# RH044_2.net
KiCad netlist of a schematic drawn in EAGLE
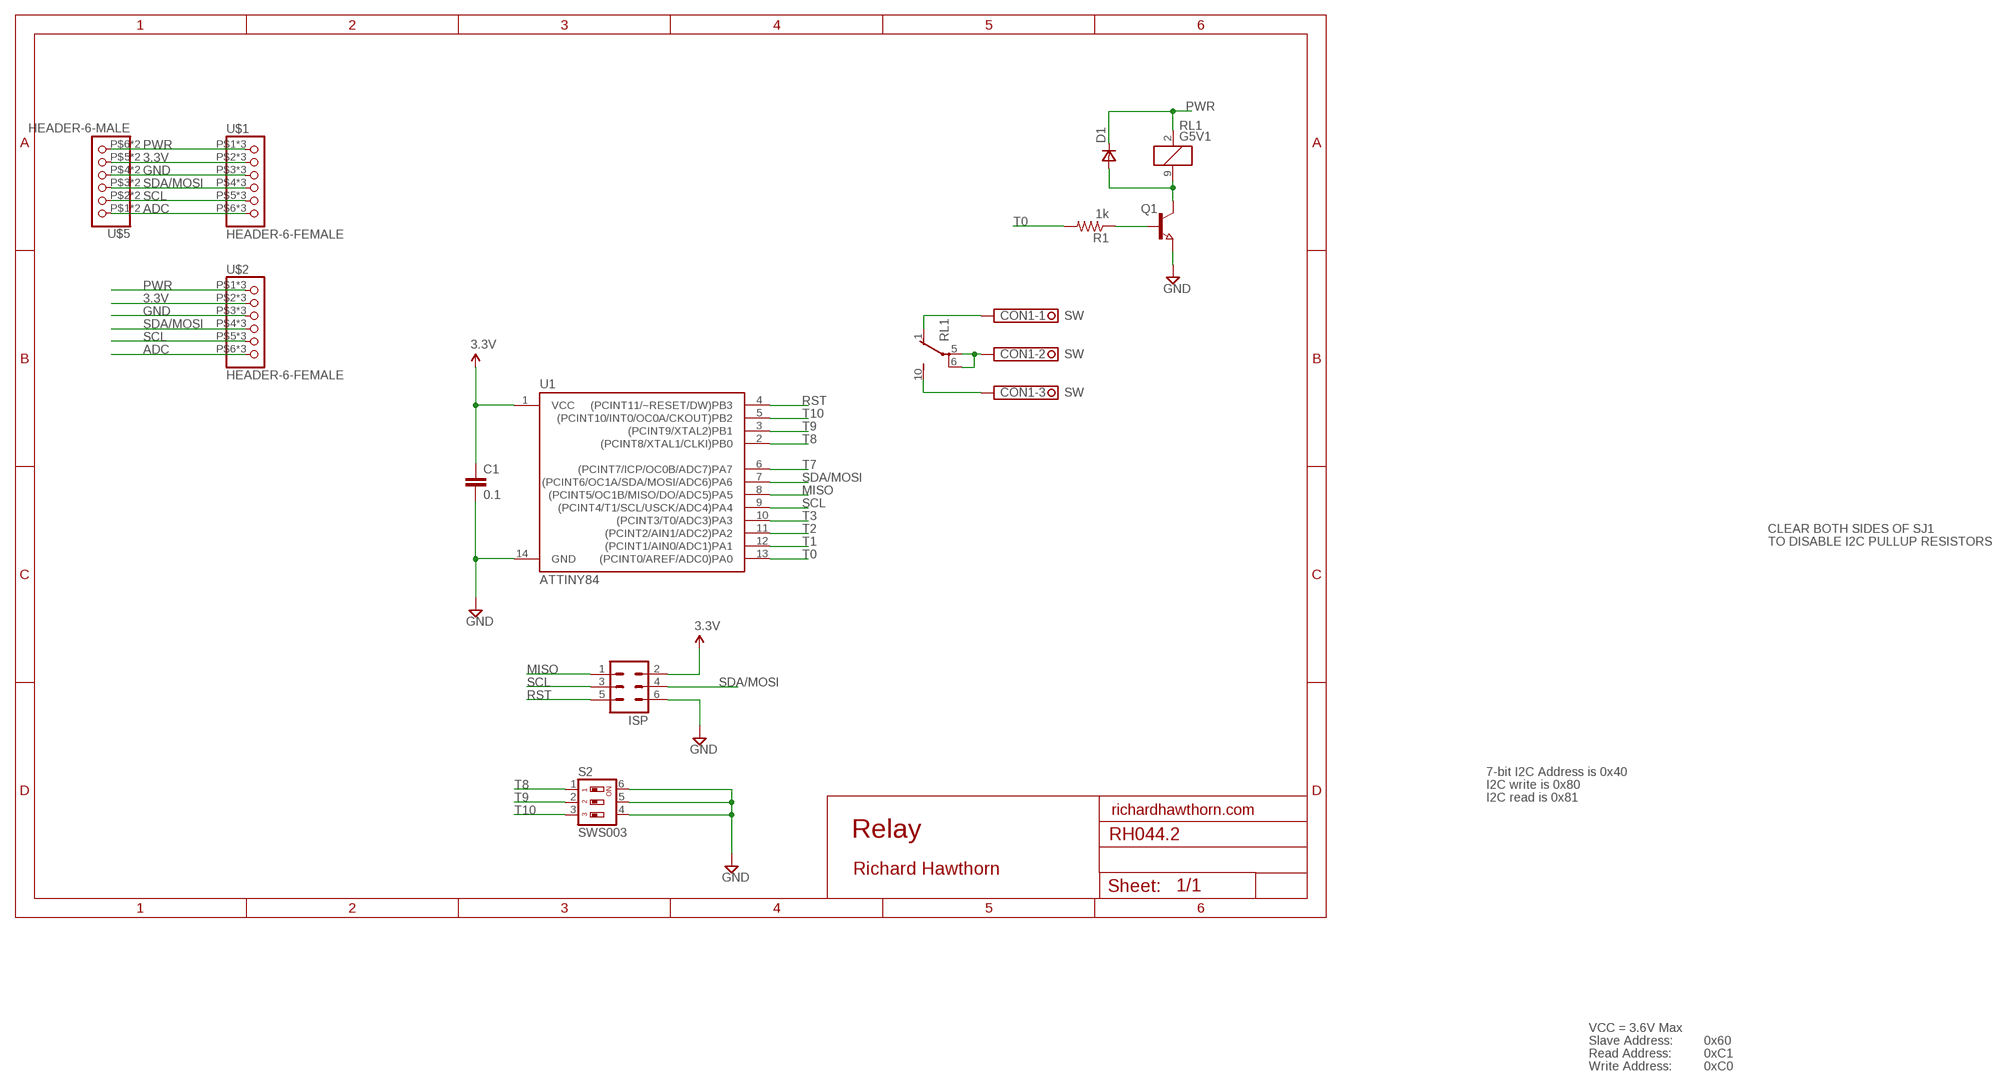
[diagram p0: schematic, sheet 1]

(export (version "E")
  (design (tool "Eeschema 10.0.6"))
  (components
    (comp (ref "C1")
      (value "0.1")
      (footprint "eagle-import:0603-CAP")
      (libsource (lib "eagle-import") (part "CAP0603-CAP"))
    )
    (comp (ref "CON1")
      (value "SW")
      (footprint "eagle-import:1751251")
      (libsource (lib "eagle-import") (part "1751251"))
    )
    (comp (ref "D1")
      (value "VAR2SOT23")
      (footprint "eagle-import:SOT-23")
      (libsource (lib "eagle-import") (part "VAR2SOT23"))
    )
    (comp (ref "ISP")
      (value "MA03-2")
      (footprint "eagle-import:MA03-2")
      (libsource (lib "eagle-import") (part "MA03-2"))
    )
    (comp (ref "Q1")
      (value "NPN-TRANSISTOR_SOT23")
      (footprint "eagle-import:SOT23")
      (libsource (lib "eagle-import") (part "NPN-TRANSISTOR_SOT23"))
    )
    (comp (ref "R1")
      (value "1k")
      (footprint "eagle-import:0603-RES")
      (libsource (lib "eagle-import") (part "RESISTOR0603-RES"))
    )
    (comp (ref "RL1")
      (value "G5V1")
      (footprint "eagle-import:G5V1")
      (fields (field (name "MPN") "G5V-1-DC24"))
      (libsource (lib "eagle-import") (part "G5V1"))
    )
    (comp (ref "S2")
      (value "SWS003")
      (footprint "eagle-import:SMS-003")
      (libsource (lib "eagle-import") (part "SWS003"))
    )
    (comp (ref "U$1")
      (value "HEADER-6-FEMALE")
      (footprint "eagle-import:2MMHEADER6")
      (libsource (lib "eagle-import") (part "HEADER-6-FEMALE"))
    )
    (comp (ref "U$2")
      (value "HEADER-6-FEMALE")
      (footprint "eagle-import:2MMHEADER6")
      (libsource (lib "eagle-import") (part "HEADER-6-FEMALE"))
    )
    (comp (ref "U$5")
      (value "HEADER-6-MALE")
      (footprint "eagle-import:2MMHEADERPIN6")
      (libsource (lib "eagle-import") (part "HEADER-6-MALE"))
    )
    (comp (ref "U1")
      (value "ATTINY84")
      (footprint "eagle-import:SO14")
      (libsource (lib "eagle-import") (part "ATTINY84"))
    )
  )
  (nets
    (net (code "1") (name "/ADC") (class "Default")
      (node (ref "U$1") (pin "P$14") (pinfunction "6_P$14") (pintype "passive"))
      (node (ref "U$1") (pin "P$22") (pinfunction "6_P$22") (pintype "passive"))
      (node (ref "U$1") (pin "P$6") (pinfunction "6_P$6") (pintype "passive"))
      (node (ref "U$2") (pin "P$14") (pinfunction "6_P$14") (pintype "passive"))
      (node (ref "U$2") (pin "P$22") (pinfunction "6_P$22") (pintype "passive"))
      (node (ref "U$2") (pin "P$6") (pinfunction "6_P$6") (pintype "passive"))
      (node (ref "U$5") (pin "P$1") (pinfunction "1_P$1") (pintype "passive"))
      (node (ref "U$5") (pin "P$9") (pinfunction "1_P$9") (pintype "passive"))
    )
    (net (code "2") (name "/MISO") (class "Default")
      (node (ref "ISP") (pin "1") (pinfunction "1_1") (pintype "passive"))
      (node (ref "U1") (pin "8") (pinfunction "(PCINT5/OC1B/MISO/DO/ADC5)PA5_8") (pintype "bidirectional"))
    )
    (net (code "3") (name "/PWR") (class "Default")
      (node (ref "D1") (pin "1") (pinfunction "C_1") (pintype "passive"))
      (node (ref "RL1") (pin "2") (pinfunction "1_2") (pintype "passive"))
      (node (ref "U$1") (pin "P$1") (pinfunction "1_P$1") (pintype "passive"))
      (node (ref "U$1") (pin "P$17") (pinfunction "1_P$17") (pintype "passive"))
      (node (ref "U$1") (pin "P$9") (pinfunction "1_P$9") (pintype "passive"))
      (node (ref "U$2") (pin "P$1") (pinfunction "1_P$1") (pintype "passive"))
      (node (ref "U$2") (pin "P$17") (pinfunction "1_P$17") (pintype "passive"))
      (node (ref "U$2") (pin "P$9") (pinfunction "1_P$9") (pintype "passive"))
      (node (ref "U$5") (pin "P$14") (pinfunction "6_P$14") (pintype "passive"))
      (node (ref "U$5") (pin "P$6") (pinfunction "6_P$6") (pintype "passive"))
    )
    (net (code "4") (name "/RST") (class "Default")
      (node (ref "ISP") (pin "5") (pinfunction "5_5") (pintype "passive"))
      (node (ref "U1") (pin "4") (pinfunction "(PCINT11/~{RESET/DW})PB3_4") (pintype "bidirectional"))
    )
    (net (code "5") (name "/SCL") (class "Default")
      (node (ref "ISP") (pin "3") (pinfunction "3_3") (pintype "passive"))
      (node (ref "U$1") (pin "P$13") (pinfunction "5_P$13") (pintype "passive"))
      (node (ref "U$1") (pin "P$21") (pinfunction "5_P$21") (pintype "passive"))
      (node (ref "U$1") (pin "P$5") (pinfunction "5_P$5") (pintype "passive"))
      (node (ref "U$2") (pin "P$13") (pinfunction "5_P$13") (pintype "passive"))
      (node (ref "U$2") (pin "P$21") (pinfunction "5_P$21") (pintype "passive"))
      (node (ref "U$2") (pin "P$5") (pinfunction "5_P$5") (pintype "passive"))
      (node (ref "U$5") (pin "P$10") (pinfunction "2_P$10") (pintype "passive"))
      (node (ref "U$5") (pin "P$2") (pinfunction "2_P$2") (pintype "passive"))
      (node (ref "U1") (pin "9") (pinfunction "(PCINT4/T1/SCL/USCK/ADC4)PA4_9") (pintype "bidirectional"))
    )
    (net (code "6") (name "/SDA{slash}MOSI") (class "Default")
      (node (ref "ISP") (pin "4") (pinfunction "4_4") (pintype "passive"))
      (node (ref "U$1") (pin "P$12") (pinfunction "4_P$12") (pintype "passive"))
      (node (ref "U$1") (pin "P$20") (pinfunction "4_P$20") (pintype "passive"))
      (node (ref "U$1") (pin "P$4") (pinfunction "4_P$4") (pintype "passive"))
      (node (ref "U$2") (pin "P$12") (pinfunction "4_P$12") (pintype "passive"))
      (node (ref "U$2") (pin "P$20") (pinfunction "4_P$20") (pintype "passive"))
      (node (ref "U$2") (pin "P$4") (pinfunction "4_P$4") (pintype "passive"))
      (node (ref "U$5") (pin "P$11") (pinfunction "3_P$11") (pintype "passive"))
      (node (ref "U$5") (pin "P$3") (pinfunction "3_P$3") (pintype "passive"))
      (node (ref "U1") (pin "7") (pinfunction "(PCINT6/OC1A/SDA/MOSI/ADC6)PA6_7") (pintype "bidirectional"))
    )
    (net (code "7") (name "/T0") (class "Default")
      (node (ref "R1") (pin "2") (pinfunction "2_2") (pintype "passive"))
      (node (ref "U1") (pin "13") (pinfunction "(PCINT0/AREF/ADC0)PA0_13") (pintype "bidirectional"))
    )
    (net (code "8") (name "/T1") (class "Default")
      (node (ref "U1") (pin "12") (pinfunction "(PCINT1/AIN0/ADC1)PA1_12") (pintype "bidirectional"))
    )
    (net (code "9") (name "/T2") (class "Default")
      (node (ref "U1") (pin "11") (pinfunction "(PCINT2/AIN1/ADC2)PA2_11") (pintype "bidirectional"))
    )
    (net (code "10") (name "/T3") (class "Default")
      (node (ref "U1") (pin "10") (pinfunction "(PCINT3/T0/ADC3)PA3_10") (pintype "bidirectional"))
    )
    (net (code "11") (name "/T7") (class "Default")
      (node (ref "U1") (pin "6") (pinfunction "(PCINT7/ICP/OC0B/ADC7)PA7_6") (pintype "bidirectional"))
    )
    (net (code "12") (name "/T8") (class "Default")
      (node (ref "S2") (pin "1") (pinfunction "1_1") (pintype "passive"))
      (node (ref "U1") (pin "2") (pinfunction "(PCINT8/XTAL1/CLKI)PB0_2") (pintype "bidirectional"))
    )
    (net (code "13") (name "/T9") (class "Default")
      (node (ref "S2") (pin "2") (pinfunction "2_2") (pintype "passive"))
      (node (ref "U1") (pin "3") (pinfunction "(PCINT9/XTAL2)PB1_3") (pintype "bidirectional"))
    )
    (net (code "14") (name "/T10") (class "Default")
      (node (ref "S2") (pin "3") (pinfunction "3_3") (pintype "passive"))
      (node (ref "U1") (pin "5") (pinfunction "(PCINT10/INT0/OC0A/CKOUT)PB2_5") (pintype "bidirectional"))
    )
    (net (code "15") (name "3.3V") (class "Default")
      (node (ref "C1") (pin "1") (pinfunction "1_1") (pintype "passive"))
      (node (ref "ISP") (pin "2") (pinfunction "2_2") (pintype "passive"))
      (node (ref "U$1") (pin "P$10") (pinfunction "2_P$10") (pintype "passive"))
      (node (ref "U$1") (pin "P$18") (pinfunction "2_P$18") (pintype "passive"))
      (node (ref "U$1") (pin "P$2") (pinfunction "2_P$2") (pintype "passive"))
      (node (ref "U$2") (pin "P$10") (pinfunction "2_P$10") (pintype "passive"))
      (node (ref "U$2") (pin "P$18") (pinfunction "2_P$18") (pintype "passive"))
      (node (ref "U$2") (pin "P$2") (pinfunction "2_P$2") (pintype "passive"))
      (node (ref "U$5") (pin "P$13") (pinfunction "5_P$13") (pintype "passive"))
      (node (ref "U$5") (pin "P$5") (pinfunction "5_P$5") (pintype "passive"))
      (node (ref "U1") (pin "1") (pinfunction "VCC_1") (pintype "bidirectional"))
    )
    (net (code "16") (name "GND") (class "Default")
      (node (ref "C1") (pin "2") (pinfunction "2_2") (pintype "passive"))
      (node (ref "ISP") (pin "6") (pinfunction "6_6") (pintype "passive"))
      (node (ref "Q1") (pin "2") (pinfunction "E_2") (pintype "passive"))
      (node (ref "S2") (pin "4") (pinfunction "4_4") (pintype "passive"))
      (node (ref "S2") (pin "5") (pinfunction "5_5") (pintype "passive"))
      (node (ref "S2") (pin "6") (pinfunction "6_6") (pintype "passive"))
      (node (ref "U$1") (pin "P$11") (pinfunction "3_P$11") (pintype "passive"))
      (node (ref "U$1") (pin "P$19") (pinfunction "3_P$19") (pintype "passive"))
      (node (ref "U$1") (pin "P$3") (pinfunction "3_P$3") (pintype "passive"))
      (node (ref "U$2") (pin "P$11") (pinfunction "3_P$11") (pintype "passive"))
      (node (ref "U$2") (pin "P$19") (pinfunction "3_P$19") (pintype "passive"))
      (node (ref "U$2") (pin "P$3") (pinfunction "3_P$3") (pintype "passive"))
      (node (ref "U$5") (pin "P$12") (pinfunction "4_P$12") (pintype "passive"))
      (node (ref "U$5") (pin "P$4") (pinfunction "4_P$4") (pintype "passive"))
      (node (ref "U1") (pin "14") (pinfunction "GND_14") (pintype "bidirectional"))
    )
    (net (code "17") (name "Net-(CON1A-K)") (class "Default")
      (node (ref "CON1") (pin "1") (pinfunction "K_1") (pintype "passive"))
      (node (ref "RL1") (pin "1") (pinfunction "O_1") (pintype "passive"))
    )
    (net (code "18") (name "Net-(CON1B-K)") (class "Default")
      (node (ref "CON1") (pin "2") (pinfunction "K_2") (pintype "passive"))
      (node (ref "RL1") (pin "5") (pinfunction "P_5") (pintype "passive"))
      (node (ref "RL1") (pin "6") (pinfunction "P_6") (pintype "passive"))
    )
    (net (code "19") (name "Net-(CON1C-K)") (class "Default")
      (node (ref "CON1") (pin "3") (pinfunction "K_3") (pintype "passive"))
      (node (ref "RL1") (pin "10") (pinfunction "S_10") (pintype "passive"))
    )
    (net (code "20") (name "Net-(D1-A)") (class "Default")
      (node (ref "D1") (pin "3") (pinfunction "A_3") (pintype "passive"))
      (node (ref "Q1") (pin "3") (pinfunction "C_3") (pintype "passive"))
      (node (ref "RL1") (pin "9") (pinfunction "2_9") (pintype "passive"))
    )
    (net (code "21") (name "Net-(Q1-B)") (class "Default")
      (node (ref "Q1") (pin "1") (pinfunction "B_1") (pintype "passive"))
      (node (ref "R1") (pin "1") (pinfunction "1_1") (pintype "passive"))
    )
  )
)
